# PCA9546_STEMMA_QT.net
KiCad netlist of a schematic drawn in EAGLE
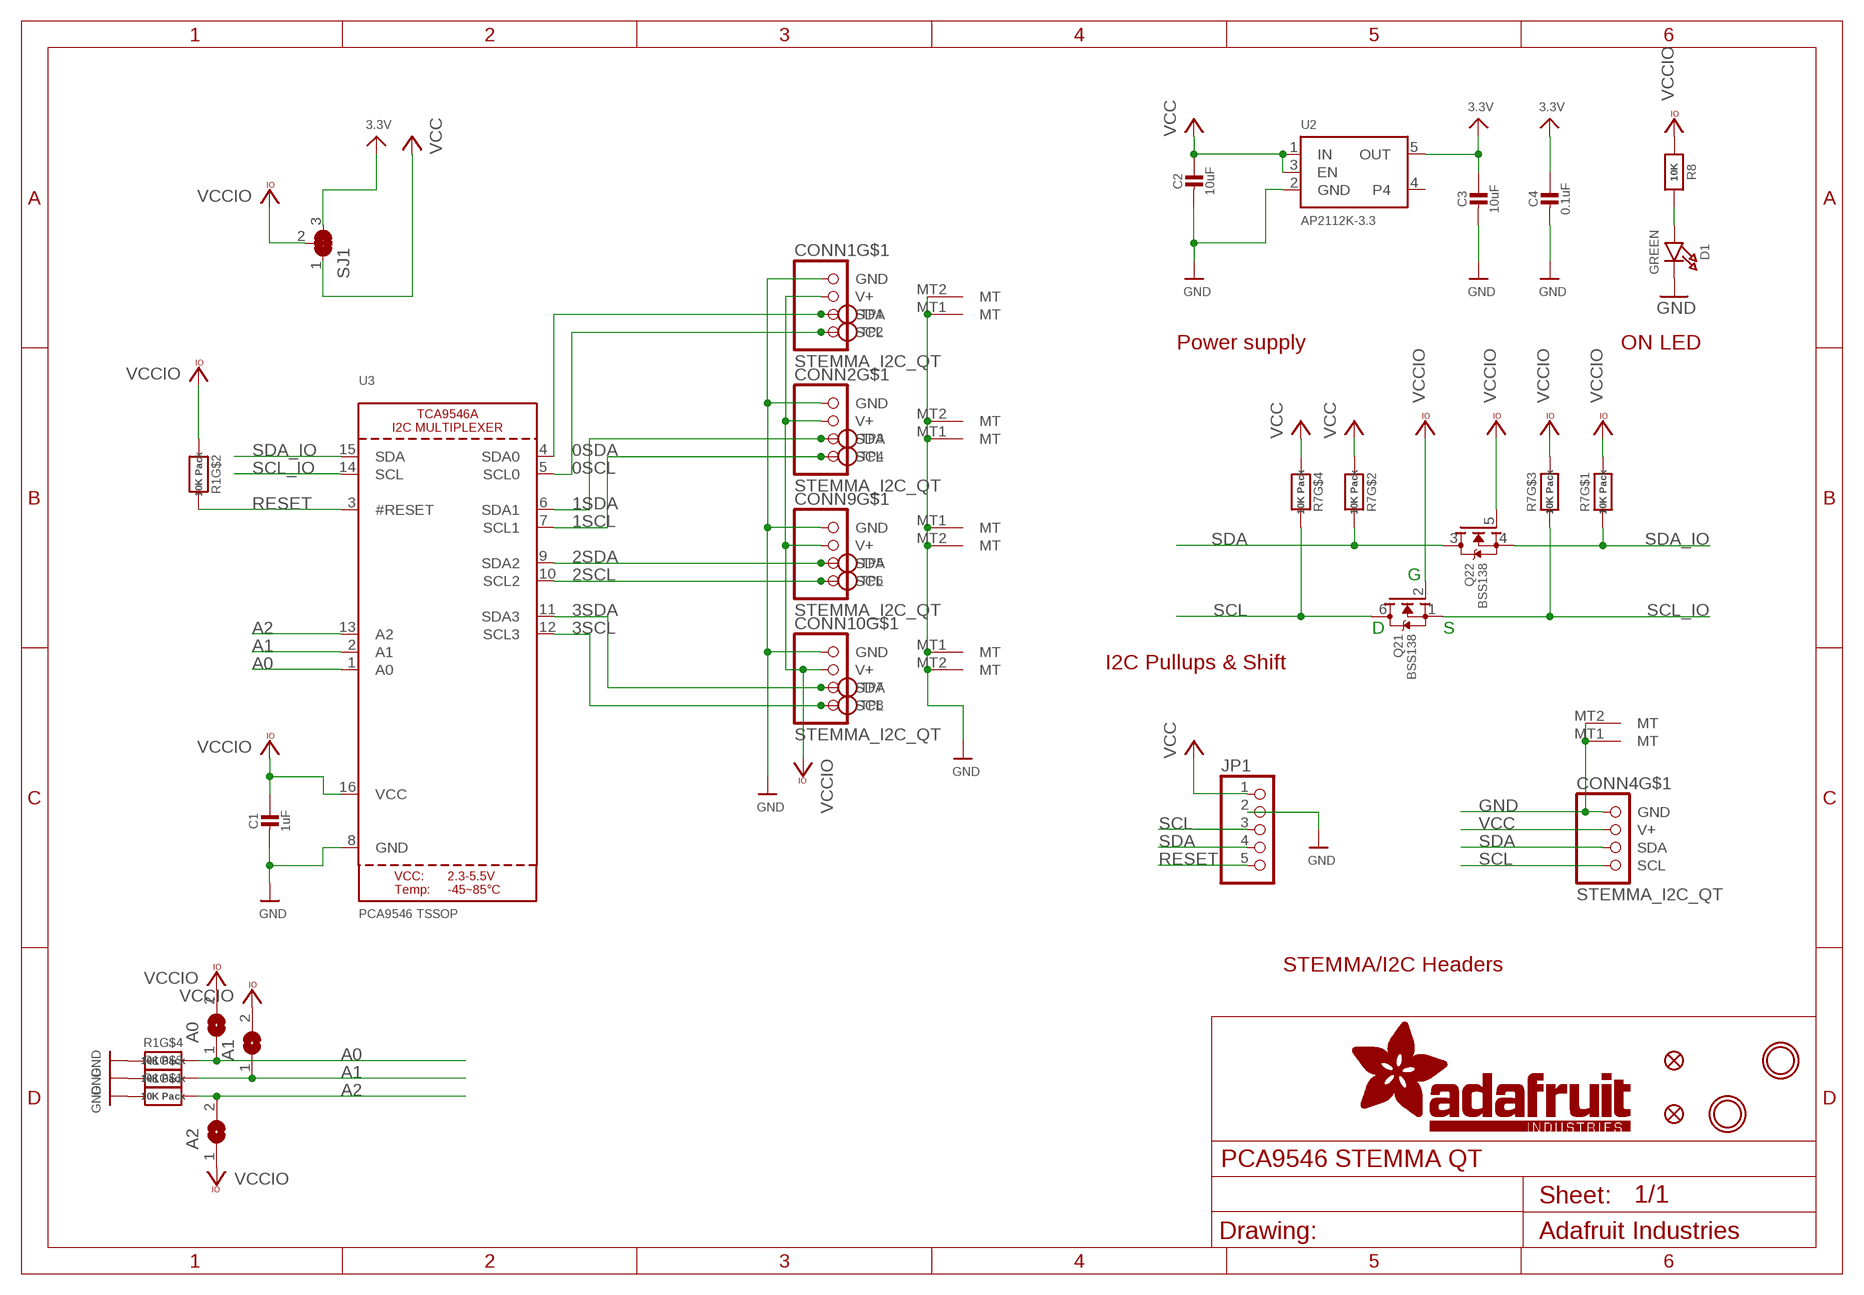
[diagram p0: schematic, sheet 1]

(export (version "E")
  (design (tool "Eeschema 10.0.6"))
  (components
    (comp (ref "A0")
      (value "SOLDERJUMPER")
      (footprint "eagle-import:SOLDERJUMPER_ARROW_NOPASTE")
      (libsource (lib "eagle-import") (part "SOLDERJUMPER"))
    )
    (comp (ref "A1")
      (value "SOLDERJUMPER")
      (footprint "eagle-import:SOLDERJUMPER_ARROW_NOPASTE")
      (libsource (lib "eagle-import") (part "SOLDERJUMPER"))
    )
    (comp (ref "A2")
      (value "SOLDERJUMPER")
      (footprint "eagle-import:SOLDERJUMPER_ARROW_NOPASTE")
      (libsource (lib "eagle-import") (part "SOLDERJUMPER"))
    )
    (comp (ref "C1")
      (value "1uF")
      (footprint "eagle-import:0603-NO")
      (libsource (lib "eagle-import") (part "CAP_CERAMIC0603_NO"))
    )
    (comp (ref "C2")
      (value "10uF")
      (footprint "eagle-import:0805-NO")
      (libsource (lib "eagle-import") (part "CAP_CERAMIC0805-NOOUTLINE"))
    )
    (comp (ref "C3")
      (value "10uF")
      (footprint "eagle-import:0805-NO")
      (libsource (lib "eagle-import") (part "CAP_CERAMIC0805-NOOUTLINE"))
    )
    (comp (ref "C4")
      (value "0.1uF")
      (footprint "eagle-import:0603-NO")
      (libsource (lib "eagle-import") (part "CAP_CERAMIC0603_NO"))
    )
    (comp (ref "CONN1")
      (value "STEMMA_I2C_QT")
      (footprint "eagle-import:JST_SH4")
      (libsource (lib "eagle-import") (part "STEMMA_I2C_QT"))
    )
    (comp (ref "CONN2")
      (value "STEMMA_I2C_QT")
      (footprint "eagle-import:JST_SH4")
      (libsource (lib "eagle-import") (part "STEMMA_I2C_QT"))
    )
    (comp (ref "CONN4")
      (value "STEMMA_I2C_QT")
      (footprint "eagle-import:JST_SH4")
      (libsource (lib "eagle-import") (part "microbuilder_STEMMA_I2C_QT"))
    )
    (comp (ref "CONN9")
      (value "STEMMA_I2C_QT")
      (footprint "eagle-import:JST_SH4")
      (libsource (lib "eagle-import") (part "STEMMA_I2C_QT"))
    )
    (comp (ref "CONN10")
      (value "STEMMA_I2C_QT")
      (footprint "eagle-import:JST_SH4")
      (libsource (lib "eagle-import") (part "STEMMA_I2C_QT"))
    )
    (comp (ref "D1")
      (value "GREEN")
      (footprint "eagle-import:CHIPLED_0603_NOOUTLINE")
      (libsource (lib "eagle-import") (part "LED0603_NOOUTLINE"))
    )
    (comp (ref "FID2")
      (value "FIDUCIAL_1MM")
      (footprint "eagle-import:FIDUCIAL_1MM")
      (libsource (lib "eagle-import") (part "FIDUCIAL_1MM"))
    )
    (comp (ref "FID4")
      (value "FIDUCIAL_1MM")
      (footprint "eagle-import:FIDUCIAL_1MM")
      (libsource (lib "eagle-import") (part "FIDUCIAL_1MM"))
    )
    (comp (ref "JP1")
      (value "HEADER-1X570MIL")
      (footprint "eagle-import:1X05_ROUND_70")
      (libsource (lib "eagle-import") (part "HEADER-1X570MIL"))
    )
    (comp (ref "Q2")
      (value "BSS138")
      (footprint "eagle-import:SOT363")
      (libsource (lib "eagle-import") (part "MOSFET-N_DUAL"))
    )
    (comp (ref "R1")
      (value "10K Pack")
      (footprint "eagle-import:RESPACK_4X0603")
      (libsource (lib "eagle-import") (part "RESISTOR_4PACK"))
    )
    (comp (ref "R7")
      (value "10K Pack")
      (footprint "eagle-import:RESPACK_4X0603")
      (libsource (lib "eagle-import") (part "RESISTOR_4PACK"))
    )
    (comp (ref "R8")
      (value "10K")
      (footprint "eagle-import:0603-NO")
      (libsource (lib "eagle-import") (part "RESISTOR_0603_NOOUT"))
    )
    (comp (ref "SJ1")
      (value "SOLDERJUMPER_2WAY")
      (footprint "eagle-import:SOLDERJUMPER_2WAY_OPEN_NOPASTE")
      (libsource (lib "eagle-import") (part "SOLDERJUMPER_2WAY"))
    )
    (comp (ref "TP1")
      (value "TESTPOINTROUND1.5MMNO")
      (footprint "eagle-import:TESTPOINT_ROUND_1.5MM_NO")
      (libsource (lib "eagle-import") (part "TESTPOINTROUND1.5MMNO"))
    )
    (comp (ref "TP2")
      (value "TESTPOINTROUND1.5MMNO")
      (footprint "eagle-import:TESTPOINT_ROUND_1.5MM_NO")
      (libsource (lib "eagle-import") (part "TESTPOINTROUND1.5MMNO"))
    )
    (comp (ref "TP3")
      (value "TESTPOINTROUND1.5MMNO")
      (footprint "eagle-import:TESTPOINT_ROUND_1.5MM_NO")
      (libsource (lib "eagle-import") (part "TESTPOINTROUND1.5MMNO"))
    )
    (comp (ref "TP4")
      (value "TESTPOINTROUND1.5MMNO")
      (footprint "eagle-import:TESTPOINT_ROUND_1.5MM_NO")
      (libsource (lib "eagle-import") (part "TESTPOINTROUND1.5MMNO"))
    )
    (comp (ref "TP5")
      (value "TESTPOINTROUND1.5MMNO")
      (footprint "eagle-import:TESTPOINT_ROUND_1.5MM_NO")
      (libsource (lib "eagle-import") (part "TESTPOINTROUND1.5MMNO"))
    )
    (comp (ref "TP6")
      (value "TESTPOINTROUND1.5MMNO")
      (footprint "eagle-import:TESTPOINT_ROUND_1.5MM_NO")
      (libsource (lib "eagle-import") (part "TESTPOINTROUND1.5MMNO"))
    )
    (comp (ref "TP7")
      (value "TESTPOINTROUND1.5MMNO")
      (footprint "eagle-import:TESTPOINT_ROUND_1.5MM_NO")
      (libsource (lib "eagle-import") (part "TESTPOINTROUND1.5MMNO"))
    )
    (comp (ref "TP8")
      (value "TESTPOINTROUND1.5MMNO")
      (footprint "eagle-import:TESTPOINT_ROUND_1.5MM_NO")
      (libsource (lib "eagle-import") (part "TESTPOINTROUND1.5MMNO"))
    )
    (comp (ref "U$19")
      (value "MOUNTINGHOLE2.5")
      (footprint "eagle-import:MOUNTINGHOLE_2.5_PLATED")
      (libsource (lib "eagle-import") (part "MOUNTINGHOLE2.5"))
    )
    (comp (ref "U$22")
      (value "MOUNTINGHOLE2.5")
      (footprint "eagle-import:MOUNTINGHOLE_2.5_PLATED")
      (libsource (lib "eagle-import") (part "MOUNTINGHOLE2.5"))
    )
    (comp (ref "U2")
      (value "AP2112K-3.3")
      (footprint "eagle-import:SOT23-5")
      (fields (field (name "JLC_ROTATION") "0"))
      (libsource (lib "eagle-import") (part "VREG_SOT23-5"))
    )
    (comp (ref "U3")
      (value "PCA9546 TSSOP")
      (footprint "eagle-import:TSSOP16")
      (libsource (lib "eagle-import") (part "XCA9546APW"))
    )
  )
  (nets
    (net (code "1") (name "/0SCL") (class "Default")
      (node (ref "CONN1") (pin "4") (pinfunction "SCL_4") (pintype "passive"))
      (node (ref "TP2") (pin "P$1") (pinfunction "P$1_P$1") (pintype "bidirectional"))
      (node (ref "U3") (pin "5") (pinfunction "SCL0_5") (pintype "bidirectional"))
    )
    (net (code "2") (name "/0SDA") (class "Default")
      (node (ref "CONN1") (pin "3") (pinfunction "SDA_3") (pintype "passive"))
      (node (ref "TP1") (pin "P$1") (pinfunction "P$1_P$1") (pintype "bidirectional"))
      (node (ref "U3") (pin "4") (pinfunction "SDA0_4") (pintype "bidirectional"))
    )
    (net (code "3") (name "/1SCL") (class "Default")
      (node (ref "CONN2") (pin "4") (pinfunction "SCL_4") (pintype "passive"))
      (node (ref "TP4") (pin "P$1") (pinfunction "P$1_P$1") (pintype "bidirectional"))
      (node (ref "U3") (pin "7") (pinfunction "SCL1_7") (pintype "bidirectional"))
    )
    (net (code "4") (name "/1SDA") (class "Default")
      (node (ref "CONN2") (pin "3") (pinfunction "SDA_3") (pintype "passive"))
      (node (ref "TP3") (pin "P$1") (pinfunction "P$1_P$1") (pintype "bidirectional"))
      (node (ref "U3") (pin "6") (pinfunction "SDA1_6") (pintype "bidirectional"))
    )
    (net (code "5") (name "/2SCL") (class "Default")
      (node (ref "CONN9") (pin "4") (pinfunction "SCL_4") (pintype "passive"))
      (node (ref "TP6") (pin "P$1") (pinfunction "P$1_P$1") (pintype "bidirectional"))
      (node (ref "U3") (pin "10") (pinfunction "SCL2_10") (pintype "bidirectional"))
    )
    (net (code "6") (name "/2SDA") (class "Default")
      (node (ref "CONN9") (pin "3") (pinfunction "SDA_3") (pintype "passive"))
      (node (ref "TP5") (pin "P$1") (pinfunction "P$1_P$1") (pintype "bidirectional"))
      (node (ref "U3") (pin "9") (pinfunction "SDA2_9") (pintype "bidirectional"))
    )
    (net (code "7") (name "/3SCL") (class "Default")
      (node (ref "CONN10") (pin "4") (pinfunction "SCL_4") (pintype "passive"))
      (node (ref "TP8") (pin "P$1") (pinfunction "P$1_P$1") (pintype "bidirectional"))
      (node (ref "U3") (pin "12") (pinfunction "SCL3_12") (pintype "bidirectional"))
    )
    (net (code "8") (name "/3SDA") (class "Default")
      (node (ref "CONN10") (pin "3") (pinfunction "SDA_3") (pintype "passive"))
      (node (ref "TP7") (pin "P$1") (pinfunction "P$1_P$1") (pintype "bidirectional"))
      (node (ref "U3") (pin "11") (pinfunction "SDA3_11") (pintype "bidirectional"))
    )
    (net (code "9") (name "/A0") (class "Default")
      (node (ref "A0") (pin "1") (pinfunction "1_1") (pintype "passive"))
      (node (ref "R1") (pin "5") (pinfunction "2_5") (pintype "passive"))
      (node (ref "U3") (pin "1") (pinfunction "A0_1") (pintype "bidirectional"))
    )
    (net (code "10") (name "/A1") (class "Default")
      (node (ref "A1") (pin "1") (pinfunction "1_1") (pintype "passive"))
      (node (ref "R1") (pin "6") (pinfunction "2_6") (pintype "passive"))
      (node (ref "U3") (pin "2") (pinfunction "A1_2") (pintype "bidirectional"))
    )
    (net (code "11") (name "/A2") (class "Default")
      (node (ref "A2") (pin "2") (pinfunction "2_2") (pintype "passive"))
      (node (ref "R1") (pin "8") (pinfunction "2_8") (pintype "passive"))
      (node (ref "U3") (pin "13") (pinfunction "A2_13") (pintype "bidirectional"))
    )
    (net (code "12") (name "/RESET") (class "Default")
      (node (ref "JP1") (pin "5") (pinfunction "5_5") (pintype "passive"))
      (node (ref "R1") (pin "7") (pinfunction "2_7") (pintype "passive"))
      (node (ref "U3") (pin "3") (pinfunction "#RESET_3") (pintype "bidirectional"))
    )
    (net (code "13") (name "/SCL") (class "Default")
      (node (ref "CONN4") (pin "4") (pinfunction "SCL_4") (pintype "passive"))
      (node (ref "JP1") (pin "3") (pinfunction "3_3") (pintype "passive"))
      (node (ref "Q2") (pin "6") (pinfunction "D_6") (pintype "bidirectional"))
      (node (ref "R7") (pin "5") (pinfunction "2_5") (pintype "passive"))
    )
    (net (code "14") (name "/SCL_IO") (class "Default")
      (node (ref "Q2") (pin "1") (pinfunction "S_1") (pintype "bidirectional"))
      (node (ref "R7") (pin "6") (pinfunction "2_6") (pintype "passive"))
      (node (ref "U3") (pin "14") (pinfunction "SCL_14") (pintype "bidirectional"))
    )
    (net (code "15") (name "/SDA") (class "Default")
      (node (ref "CONN4") (pin "3") (pinfunction "SDA_3") (pintype "passive"))
      (node (ref "JP1") (pin "4") (pinfunction "4_4") (pintype "passive"))
      (node (ref "Q2") (pin "3") (pinfunction "D_3") (pintype "bidirectional"))
      (node (ref "R7") (pin "7") (pinfunction "2_7") (pintype "passive"))
    )
    (net (code "16") (name "/SDA_IO") (class "Default")
      (node (ref "Q2") (pin "4") (pinfunction "S_4") (pintype "bidirectional"))
      (node (ref "R7") (pin "8") (pinfunction "2_8") (pintype "passive"))
      (node (ref "U3") (pin "15") (pinfunction "SDA_15") (pintype "bidirectional"))
    )
    (net (code "17") (name "3.3V") (class "Default")
      (node (ref "C3") (pin "1") (pinfunction "1_1") (pintype "passive"))
      (node (ref "C4") (pin "1") (pinfunction "1_1") (pintype "passive"))
      (node (ref "SJ1") (pin "3") (pinfunction "3_3") (pintype "passive"))
      (node (ref "U2") (pin "5") (pinfunction "OUT_5") (pintype "power_in"))
    )
    (net (code "18") (name "GND") (class "Default")
      (node (ref "C1") (pin "2") (pinfunction "2_2") (pintype "passive"))
      (node (ref "C2") (pin "2") (pinfunction "2_2") (pintype "passive"))
      (node (ref "C3") (pin "2") (pinfunction "2_2") (pintype "passive"))
      (node (ref "C4") (pin "2") (pinfunction "2_2") (pintype "passive"))
      (node (ref "CONN1") (pin "1") (pinfunction "GND_1") (pintype "passive"))
      (node (ref "CONN1") (pin "MT1") (pinfunction "MT_MT1") (pintype "bidirectional"))
      (node (ref "CONN1") (pin "MT2") (pinfunction "MT_MT2") (pintype "bidirectional"))
      (node (ref "CONN10") (pin "1") (pinfunction "GND_1") (pintype "passive"))
      (node (ref "CONN10") (pin "MT1") (pinfunction "MT_MT1") (pintype "bidirectional"))
      (node (ref "CONN10") (pin "MT2") (pinfunction "MT_MT2") (pintype "bidirectional"))
      (node (ref "CONN2") (pin "1") (pinfunction "GND_1") (pintype "passive"))
      (node (ref "CONN2") (pin "MT1") (pinfunction "MT_MT1") (pintype "bidirectional"))
      (node (ref "CONN2") (pin "MT2") (pinfunction "MT_MT2") (pintype "bidirectional"))
      (node (ref "CONN4") (pin "1") (pinfunction "GND_1") (pintype "passive"))
      (node (ref "CONN4") (pin "MT1") (pinfunction "MT_MT1") (pintype "bidirectional"))
      (node (ref "CONN4") (pin "MT2") (pinfunction "MT_MT2") (pintype "bidirectional"))
      (node (ref "CONN9") (pin "1") (pinfunction "GND_1") (pintype "passive"))
      (node (ref "CONN9") (pin "MT1") (pinfunction "MT_MT1") (pintype "bidirectional"))
      (node (ref "CONN9") (pin "MT2") (pinfunction "MT_MT2") (pintype "bidirectional"))
      (node (ref "D1") (pin "C") (pinfunction "C_C") (pintype "passive"))
      (node (ref "JP1") (pin "2") (pinfunction "2_2") (pintype "passive"))
      (node (ref "R1") (pin "1") (pinfunction "1_1") (pintype "passive"))
      (node (ref "R1") (pin "3") (pinfunction "1_3") (pintype "passive"))
      (node (ref "R1") (pin "4") (pinfunction "1_4") (pintype "passive"))
      (node (ref "U2") (pin "2") (pinfunction "GND_2") (pintype "power_in"))
      (node (ref "U3") (pin "8") (pinfunction "GND_8") (pintype "bidirectional"))
    )
    (net (code "19") (name "Net-(D1-PadA)") (class "Default")
      (node (ref "D1") (pin "A") (pinfunction "A_A") (pintype "passive"))
      (node (ref "R8") (pin "2") (pinfunction "2_2") (pintype "passive"))
    )
    (net (code "20") (name "VCC") (class "Default")
      (node (ref "C2") (pin "1") (pinfunction "1_1") (pintype "passive"))
      (node (ref "CONN4") (pin "2") (pinfunction "V+_2") (pintype "passive"))
      (node (ref "JP1") (pin "1") (pinfunction "1_1") (pintype "passive"))
      (node (ref "R7") (pin "2") (pinfunction "1_2") (pintype "passive"))
      (node (ref "R7") (pin "4") (pinfunction "1_4") (pintype "passive"))
      (node (ref "SJ1") (pin "1") (pinfunction "1_1") (pintype "passive"))
      (node (ref "U2") (pin "1") (pinfunction "IN_1") (pintype "power_in"))
      (node (ref "U2") (pin "3") (pinfunction "EN_3") (pintype "input"))
    )
    (net (code "21") (name "VCCIO") (class "Default")
      (node (ref "A0") (pin "2") (pinfunction "2_2") (pintype "passive"))
      (node (ref "A1") (pin "2") (pinfunction "2_2") (pintype "passive"))
      (node (ref "A2") (pin "1") (pinfunction "1_1") (pintype "passive"))
      (node (ref "C1") (pin "1") (pinfunction "1_1") (pintype "passive"))
      (node (ref "CONN1") (pin "2") (pinfunction "V+_2") (pintype "passive"))
      (node (ref "CONN10") (pin "2") (pinfunction "V+_2") (pintype "passive"))
      (node (ref "CONN2") (pin "2") (pinfunction "V+_2") (pintype "passive"))
      (node (ref "CONN9") (pin "2") (pinfunction "V+_2") (pintype "passive"))
      (node (ref "Q2") (pin "2") (pinfunction "G_2") (pintype "bidirectional"))
      (node (ref "Q2") (pin "5") (pinfunction "G_5") (pintype "bidirectional"))
      (node (ref "R1") (pin "2") (pinfunction "1_2") (pintype "passive"))
      (node (ref "R7") (pin "1") (pinfunction "1_1") (pintype "passive"))
      (node (ref "R7") (pin "3") (pinfunction "1_3") (pintype "passive"))
      (node (ref "R8") (pin "1") (pinfunction "1_1") (pintype "passive"))
      (node (ref "SJ1") (pin "2") (pinfunction "2_2") (pintype "passive"))
      (node (ref "U3") (pin "16") (pinfunction "VCC_16") (pintype "bidirectional"))
    )
    (net (code "22") (name "unconnected-(U2-P4-Pad4)") (class "Default")
      (node (ref "U2") (pin "4") (pinfunction "P4_4") (pintype "bidirectional"))
    )
  )
)
